# MCU.net
KiCad netlist of a schematic drawn in Altium Designer
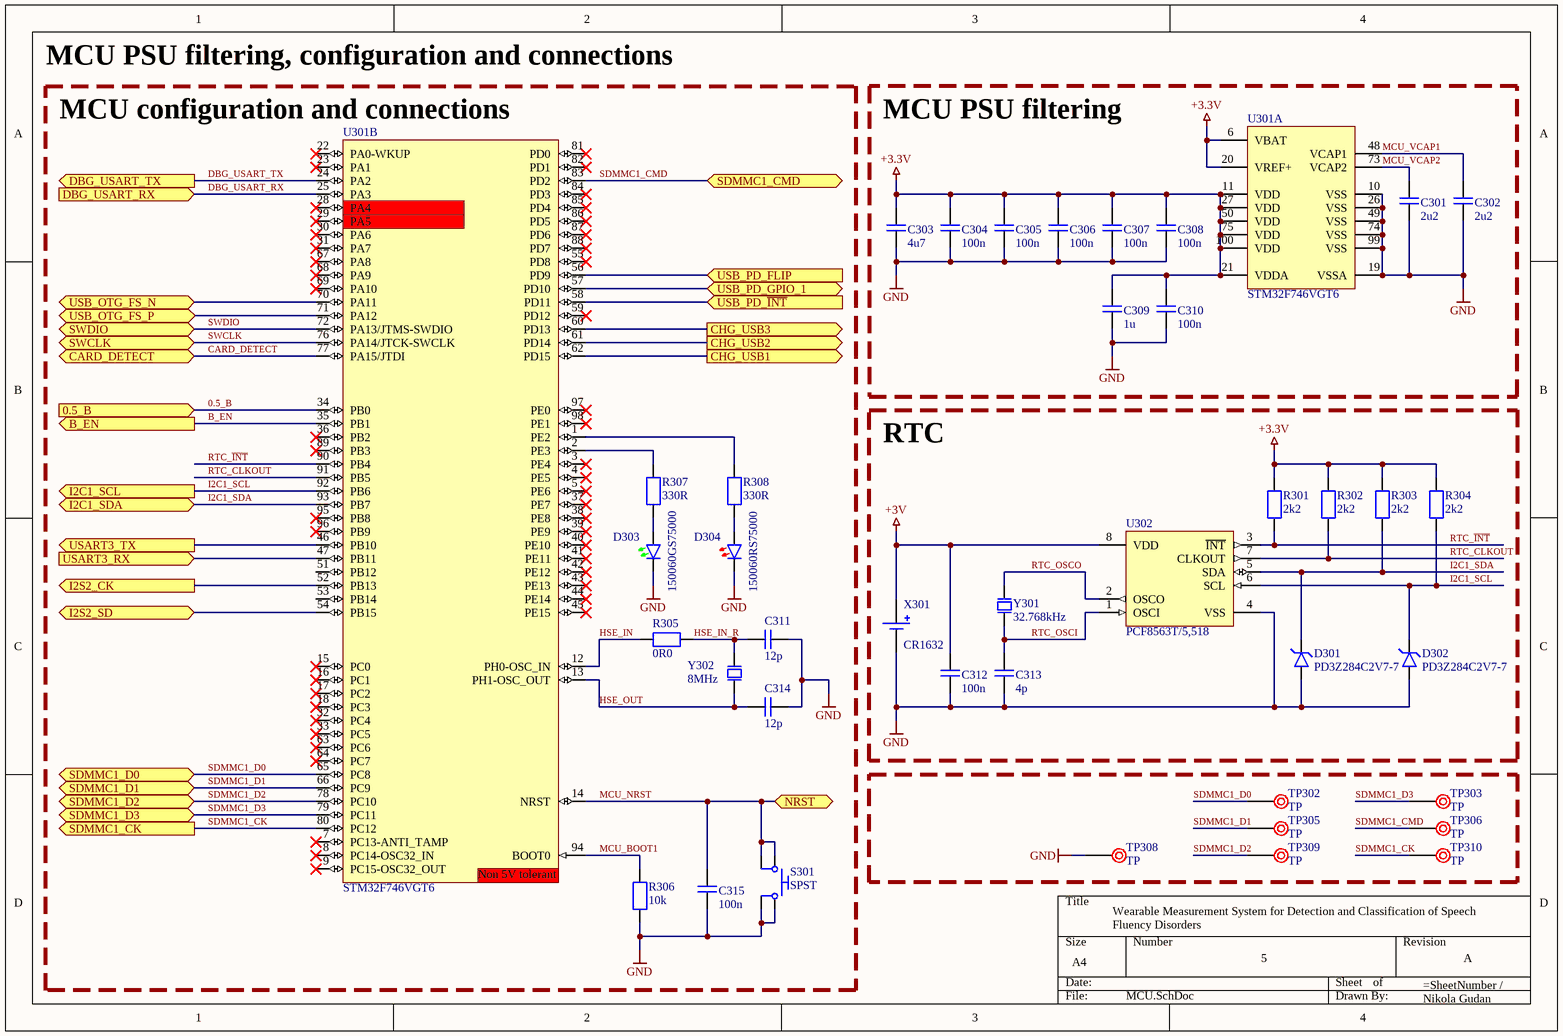
[diagram p0: MCU.SchDoc]

(export (version "E")
  (design (tool "Eeschema 10.0.6"))
  (components
    (comp (ref "C301")
      (value "2u2")
      (footprint "CAPC0603")
      (description "Ceramic capacitor, VAL?,  VOL?, DIEL?")
      (fields (field (name "MFR") "?") (field (name "CHECKED") "Yes"))
      (libsource (lib "NG_Passive") (part "CAPC0603"))
    )
    (comp (ref "C302")
      (value "2u2")
      (footprint "CAPC0603")
      (description "Ceramic capacitor, VAL?,  VOL?, DIEL?")
      (fields (field (name "MFR") "?") (field (name "CHECKED") "Yes"))
      (libsource (lib "NG_Passive") (part "CAPC0603"))
    )
    (comp (ref "C303")
      (value "4u7")
      (footprint "CAPC0603")
      (description "Ceramic capacitor, VAL?,  VOL?, DIEL?")
      (fields (field (name "MFR") "?") (field (name "CHECKED") "Yes"))
      (libsource (lib "NG_Passive") (part "CAPC0603"))
    )
    (comp (ref "C304")
      (value "100n")
      (footprint "CAPC0603")
      (description "Ceramic capacitor, VAL?,  VOL?, DIEL?")
      (fields (field (name "MFR") "?") (field (name "CHECKED") "Yes"))
      (libsource (lib "NG_Passive") (part "CAPC0603"))
    )
    (comp (ref "C305")
      (value "100n")
      (footprint "CAPC0603")
      (description "Ceramic capacitor, VAL?,  VOL?, DIEL?")
      (fields (field (name "MFR") "?") (field (name "CHECKED") "Yes"))
      (libsource (lib "NG_Passive") (part "CAPC0603"))
    )
    (comp (ref "C306")
      (value "100n")
      (footprint "CAPC0603")
      (description "Ceramic capacitor, VAL?,  VOL?, DIEL?")
      (fields (field (name "MFR") "?") (field (name "CHECKED") "Yes"))
      (libsource (lib "NG_Passive") (part "CAPC0603"))
    )
    (comp (ref "C307")
      (value "100n")
      (footprint "CAPC0603")
      (description "Ceramic capacitor, VAL?,  VOL?, DIEL?")
      (fields (field (name "MFR") "?") (field (name "CHECKED") "Yes"))
      (libsource (lib "NG_Passive") (part "CAPC0603"))
    )
    (comp (ref "C308")
      (value "100n")
      (footprint "CAPC0603")
      (description "Ceramic capacitor, VAL?,  VOL?, DIEL?")
      (fields (field (name "MFR") "?") (field (name "CHECKED") "Yes"))
      (libsource (lib "NG_Passive") (part "CAPC0603"))
    )
    (comp (ref "C309")
      (value "1u")
      (footprint "CAPC0603")
      (description "Ceramic capacitor, VAL?,  VOL?, DIEL?")
      (fields (field (name "MFR") "?") (field (name "CHECKED") "Yes"))
      (libsource (lib "NG_Passive") (part "CAPC0603"))
    )
    (comp (ref "C310")
      (value "100n")
      (footprint "CAPC0603")
      (description "Ceramic capacitor, VAL?,  VOL?, DIEL?")
      (fields (field (name "MFR") "?") (field (name "CHECKED") "Yes"))
      (libsource (lib "NG_Passive") (part "CAPC0603"))
    )
    (comp (ref "C311")
      (value "12p")
      (footprint "CAPC0603")
      (description "Ceramic capacitor, VAL?,  VOL?, DIEL?")
      (fields (field (name "MFR") "?") (field (name "CHECKED") "Yes"))
      (libsource (lib "NG_Passive") (part "CAPC0603"))
    )
    (comp (ref "C312")
      (value "100n")
      (footprint "CAPC0603")
      (description "Ceramic capacitor, VAL?,  VOL?, DIEL?")
      (fields (field (name "MFR") "?") (field (name "CHECKED") "Yes"))
      (libsource (lib "NG_Passive") (part "CAPC0603"))
    )
    (comp (ref "C313")
      (value "4p")
      (footprint "CAPC0603")
      (description "Ceramic capacitor, VAL?,  VOL?, DIEL?")
      (fields (field (name "MFR") "?") (field (name "CHECKED") "Yes"))
      (libsource (lib "NG_Passive") (part "CAPC0603"))
    )
    (comp (ref "C314")
      (value "12p")
      (footprint "CAPC0603")
      (description "Ceramic capacitor, VAL?,  VOL?, DIEL?")
      (fields (field (name "MFR") "?") (field (name "CHECKED") "Yes"))
      (libsource (lib "NG_Passive") (part "CAPC0603"))
    )
    (comp (ref "C315")
      (value "100n")
      (footprint "CAPC0603")
      (description "Ceramic capacitor, VAL?,  VOL?, DIEL?")
      (fields (field (name "MFR") "?") (field (name "CHECKED") "Yes"))
      (libsource (lib "NG_Passive") (part "CAPC0603"))
    )
    (comp (ref "D301")
      (value "PD3Z284C2V7-7")
      (footprint "PowerDI323")
      (description "Zener Dioode, 2.7V, 500mW")
      (fields
        (field (name "MFR") "Diodes Incorporated")
        (field (name "LCSC PART NUMBER") "C531171")
        (field (name "CHECKED") "Yes")
      )
      (libsource (lib "NG_Active") (part "PD3Z284C2V7-7"))
    )
    (comp (ref "D302")
      (value "PD3Z284C2V7-7")
      (footprint "PowerDI323")
      (description "Zener Dioode, 2.7V, 500mW")
      (fields
        (field (name "MFR") "Diodes Incorporated")
        (field (name "LCSC PART NUMBER") "C531171")
        (field (name "CHECKED") "Yes")
      )
      (libsource (lib "NG_Active") (part "PD3Z284C2V7-7"))
    )
    (comp (ref "D303")
      (value "150060GS75000")
      (footprint "LED0603")
      (description "LED Green, 2.1V, 20mA")
      (fields
        (field (name "MFR") "Würth Elektronik")
        (field (name "LCSC PART NUMBER") "C913102")
        (field (name "CHECKED") "Yes")
      )
      (libsource (lib "NG_Active") (part "LTST-C194KGKT"))
    )
    (comp (ref "D304")
      (value "150060RS75000")
      (footprint "LED0603")
      (description "LED Red, 2.3V, 20mA")
      (fields
        (field (name "MFR") "Würth Elektronik")
        (field (name "LCSC PART NUMBER") "C497931")
        (field (name "CHECKED") "Yes")
      )
      (libsource (lib "NG_Active") (part "HL-PST-1608S9AC-04"))
    )
    (comp (ref "R301")
      (value "2k2")
      (footprint "RESC0603")
      (description "Thick film resistor, VAL?, POW?")
      (fields (field (name "MFR") "?") (field (name "CHECKED") "Yes"))
      (libsource (lib "NG_Passive") (part "RES0603"))
    )
    (comp (ref "R302")
      (value "2k2")
      (footprint "RESC0603")
      (description "Thick film resistor, VAL?, POW?")
      (fields (field (name "MFR") "?") (field (name "CHECKED") "Yes"))
      (libsource (lib "NG_Passive") (part "RES0603"))
    )
    (comp (ref "R303")
      (value "2k2")
      (footprint "RESC0603")
      (description "Thick film resistor, VAL?, POW?")
      (fields (field (name "MFR") "?") (field (name "CHECKED") "Yes"))
      (libsource (lib "NG_Passive") (part "RES0603"))
    )
    (comp (ref "R304")
      (value "2k2")
      (footprint "RESC0603")
      (description "Thick film resistor, VAL?, POW?")
      (fields (field (name "MFR") "?") (field (name "CHECKED") "Yes"))
      (libsource (lib "NG_Passive") (part "RES0603"))
    )
    (comp (ref "R305")
      (value "0R0")
      (footprint "RESC0603")
      (description "Thick film resistor, VAL?, POW?")
      (fields (field (name "MFR") "?") (field (name "CHECKED") "Yes"))
      (libsource (lib "NG_Passive") (part "RES0603"))
    )
    (comp (ref "R306")
      (value "10k")
      (footprint "RESC0603")
      (description "Thick film resistor, VAL?, POW?")
      (fields (field (name "MFR") "?") (field (name "CHECKED") "Yes"))
      (libsource (lib "NG_Passive") (part "RES0603"))
    )
    (comp (ref "R307")
      (value "330R")
      (footprint "RESC0603")
      (description "Thick film resistor, VAL?, POW?")
      (fields (field (name "MFR") "?") (field (name "CHECKED") "Yes"))
      (libsource (lib "NG_Passive") (part "RES0603"))
    )
    (comp (ref "R308")
      (value "330R")
      (footprint "RESC0603")
      (description "Thick film resistor, VAL?, POW?")
      (fields (field (name "MFR") "?") (field (name "CHECKED") "Yes"))
      (libsource (lib "NG_Passive") (part "RES0603"))
    )
    (comp (ref "S301")
      (value "SPST")
      (footprint "SW_TSA063G60-250")
      (description "TACT SW, SPST, NO")
      (fields
        (field (name "MFR") "C&K")
        (field (name "LCSC PART NUMBER") "C294566")
        (field (name "CHECKED") "Yes")
      )
      (libsource (lib "NG_Mechanical") (part "TACT SW"))
    )
    (comp (ref "TP302")
      (value "TP")
      (footprint "TESTPOINT")
      (description "Testpoint")
      (fields
        (field (name "MFR") "Keystone")
        (field (name "LCSC PART NUMBER") "C238122")
        (field (name "CHECKED") "Yes")
      )
      (libsource (lib "NG_Mechanical") (part "TESTPOINT"))
    )
    (comp (ref "TP303")
      (value "TP")
      (footprint "TESTPOINT")
      (description "Testpoint")
      (fields
        (field (name "MFR") "Keystone")
        (field (name "LCSC PART NUMBER") "C238122")
        (field (name "CHECKED") "Yes")
      )
      (libsource (lib "NG_Mechanical") (part "TESTPOINT"))
    )
    (comp (ref "TP305")
      (value "TP")
      (footprint "TESTPOINT")
      (description "Testpoint")
      (fields
        (field (name "MFR") "Keystone")
        (field (name "LCSC PART NUMBER") "C238122")
        (field (name "CHECKED") "Yes")
      )
      (libsource (lib "NG_Mechanical") (part "TESTPOINT"))
    )
    (comp (ref "TP306")
      (value "TP")
      (footprint "TESTPOINT")
      (description "Testpoint")
      (fields
        (field (name "MFR") "Keystone")
        (field (name "LCSC PART NUMBER") "C238122")
        (field (name "CHECKED") "Yes")
      )
      (libsource (lib "NG_Mechanical") (part "TESTPOINT"))
    )
    (comp (ref "TP308")
      (value "TP")
      (footprint "TESTPOINT")
      (description "Testpoint")
      (fields
        (field (name "MFR") "Keystone")
        (field (name "LCSC PART NUMBER") "C238122")
        (field (name "CHECKED") "Yes")
      )
      (libsource (lib "NG_Mechanical") (part "TESTPOINT"))
    )
    (comp (ref "TP309")
      (value "TP")
      (footprint "TESTPOINT")
      (description "Testpoint")
      (fields
        (field (name "MFR") "Keystone")
        (field (name "LCSC PART NUMBER") "C238122")
        (field (name "CHECKED") "Yes")
      )
      (libsource (lib "NG_Mechanical") (part "TESTPOINT"))
    )
    (comp (ref "TP310")
      (value "TP")
      (footprint "TESTPOINT")
      (description "Testpoint")
      (fields
        (field (name "MFR") "Keystone")
        (field (name "LCSC PART NUMBER") "C238122")
        (field (name "CHECKED") "Yes")
      )
      (libsource (lib "NG_Mechanical") (part "TESTPOINT"))
    )
    (comp (ref "U301")
      (value "STM32F746VGT6")
      (footprint "QFP50P1600X1600X160-100")
      (fields
        (field (name "MFR") "STMicroelectronics")
        (field (name "LCSC PART NUMBER") "C87664")
        (field (name "CHECKED") "Yes")
      )
      (libsource (lib "NG_Digital") (part "STM32F746VGT6"))
    )
    (comp (ref "U302")
      (value "PCF8563T/5,518")
      (footprint "SOIC127P610X175-8")
      (description "IC RTC CLOCK/CALENDAR I2C 8SO")
      (fields
        (field (name "MFR") "NXP USA Inc.")
        (field (name "LCSC PART NUMBER") "C7440")
        (field (name "CHECKED") "Yes")
      )
      (libsource (lib "NG_Digital") (part "PCF8563T/5,518"))
    )
    (comp (ref "X301")
      (value "CR1632")
      (footprint "BAT_504TR")
      (description "CR1632 Battery Holder")
      (fields
        (field (name "MFR") "Keystone Electronics")
        (field (name "LCSC PART NUMBER") "C964735")
        (field (name "CHECKED") "Yes")
      )
      (libsource (lib "NG_Mechanical") (part "CR1632"))
    )
    (comp (ref "Y301")
      (value "32.768kHz")
      (footprint "XTAL320X150X80")
      (description "Crystal, 32.768Hz, 9pF, 50kOhms")
      (fields
        (field (name "MFR") "Seiko Epson")
        (field (name "LCSC PART NUMBER") "C1987155")
        (field (name "CHECKED") "Yes")
      )
      (libsource (lib "NG_Passive") (part "X1A0001410002"))
    )
    (comp (ref "Y302")
      (value "8MHz")
      (footprint "XTAL800X450X180")
      (description "Crystal, 8MHz, 8pF, 200Ohms")
      (fields
        (field (name "MFR") "NDK")
        (field (name "LCSC PART NUMBER") "C1985641")
        (field (name "CHECKED") "Yes")
      )
      (libsource (lib "NG_Passive") (part "NX8045GB-8.000000MHZ"))
    )
  )
  (nets
    (net (code "1") (name "+3.3V") (class "Default")
      (node (ref "C303") (pin "2") (pinfunction "2_2") (pintype "passive"))
      (node (ref "C304") (pin "2") (pinfunction "2_2") (pintype "passive"))
      (node (ref "C305") (pin "2") (pinfunction "2_2") (pintype "passive"))
      (node (ref "C306") (pin "2") (pinfunction "2_2") (pintype "passive"))
      (node (ref "C307") (pin "2") (pinfunction "2_2") (pintype "passive"))
      (node (ref "C308") (pin "2") (pinfunction "2_2") (pintype "passive"))
      (node (ref "C309") (pin "2") (pinfunction "2_2") (pintype "passive"))
      (node (ref "C310") (pin "2") (pinfunction "2_2") (pintype "passive"))
      (node (ref "R301") (pin "2") (pinfunction "2_2") (pintype "passive"))
      (node (ref "R302") (pin "2") (pinfunction "2_2") (pintype "passive"))
      (node (ref "R303") (pin "2") (pinfunction "2_2") (pintype "passive"))
      (node (ref "R304") (pin "2") (pinfunction "2_2") (pintype "passive"))
      (node (ref "U301") (pin "100") (pinfunction "VDD_100") (pintype "power_in"))
      (node (ref "U301") (pin "11") (pinfunction "VDD_11") (pintype "power_in"))
      (node (ref "U301") (pin "20") (pinfunction "VREF+_20") (pintype "power_in"))
      (node (ref "U301") (pin "21") (pinfunction "VDDA_21") (pintype "power_in"))
      (node (ref "U301") (pin "27") (pinfunction "VDD_27") (pintype "power_in"))
      (node (ref "U301") (pin "50") (pinfunction "VDD_50") (pintype "power_in"))
      (node (ref "U301") (pin "6") (pinfunction "VBAT_6") (pintype "power_in"))
      (node (ref "U301") (pin "75") (pinfunction "VDD_75") (pintype "power_in"))
    )
    (net (code "2") (name "+3V") (class "Default")
      (node (ref "C312") (pin "2") (pinfunction "2_2") (pintype "passive"))
      (node (ref "U302") (pin "8") (pinfunction "VDD_8") (pintype "power_in"))
      (node (ref "X301") (pin "1") (pinfunction "P_1") (pintype "power_in"))
    )
    (net (code "3") (name "/0.5_B") (class "Default")
      (node (ref "U301") (pin "34") (pinfunction "PB0_34") (pintype "bidirectional"))
    )
    (net (code "4") (name "/B_EN") (class "Default")
      (node (ref "U301") (pin "35") (pinfunction "PB1_35") (pintype "bidirectional"))
    )
    (net (code "5") (name "/CARD_DETECT") (class "Default")
      (node (ref "U301") (pin "77") (pinfunction "PA15/JTDI_77") (pintype "bidirectional"))
    )
    (net (code "6") (name "/CHG_USB1") (class "Default")
      (node (ref "U301") (pin "62") (pinfunction "PD15_62") (pintype "bidirectional"))
    )
    (net (code "7") (name "/CHG_USB2") (class "Default")
      (node (ref "U301") (pin "61") (pinfunction "PD14_61") (pintype "bidirectional"))
    )
    (net (code "8") (name "/CHG_USB3") (class "Default")
      (node (ref "U301") (pin "60") (pinfunction "PD13_60") (pintype "bidirectional"))
    )
    (net (code "9") (name "/DBG_USART_RX") (class "Default")
      (node (ref "U301") (pin "25") (pinfunction "PA3_25") (pintype "bidirectional"))
    )
    (net (code "10") (name "/DBG_USART_TX") (class "Default")
      (node (ref "U301") (pin "24") (pinfunction "PA2_24") (pintype "bidirectional"))
    )
    (net (code "11") (name "/HSE_IN") (class "Default")
      (node (ref "R305") (pin "2") (pinfunction "2_2") (pintype "passive"))
      (node (ref "U301") (pin "12") (pinfunction "PH0-OSC_IN_12") (pintype "bidirectional"))
    )
    (net (code "12") (name "/HSE_IN_R") (class "Default")
      (node (ref "C311") (pin "1") (pinfunction "1_1") (pintype "passive"))
      (node (ref "R305") (pin "1") (pinfunction "1_1") (pintype "passive"))
      (node (ref "Y302") (pin "2") (pinfunction "2_2") (pintype "passive"))
    )
    (net (code "13") (name "/HSE_OUT") (class "Default")
      (node (ref "C314") (pin "1") (pinfunction "1_1") (pintype "passive"))
      (node (ref "U301") (pin "13") (pinfunction "PH1-OSC_OUT_13") (pintype "bidirectional"))
      (node (ref "Y302") (pin "1") (pinfunction "1_1") (pintype "passive"))
    )
    (net (code "14") (name "/I2C1_SCL") (class "Default")
      (node (ref "D302") (pin "1") (pinfunction "1_1") (pintype "passive"))
      (node (ref "R304") (pin "1") (pinfunction "1_1") (pintype "passive"))
      (node (ref "U301") (pin "92") (pinfunction "PB6_92") (pintype "bidirectional"))
      (node (ref "U302") (pin "6") (pinfunction "SCL_6") (pintype "input"))
    )
    (net (code "15") (name "/I2C1_SDA") (class "Default")
      (node (ref "D301") (pin "1") (pinfunction "1_1") (pintype "passive"))
      (node (ref "R303") (pin "1") (pinfunction "1_1") (pintype "passive"))
      (node (ref "U301") (pin "93") (pinfunction "PB7_93") (pintype "bidirectional"))
      (node (ref "U302") (pin "5") (pinfunction "SDA_5") (pintype "bidirectional"))
    )
    (net (code "16") (name "/I2S2_CK") (class "Default")
      (node (ref "U301") (pin "52") (pinfunction "PB13_52") (pintype "bidirectional"))
    )
    (net (code "17") (name "/I2S2_SD") (class "Default")
      (node (ref "U301") (pin "54") (pinfunction "PB15_54") (pintype "bidirectional"))
    )
    (net (code "18") (name "/MCU_BOOT1") (class "Default")
      (node (ref "R306") (pin "2") (pinfunction "2_2") (pintype "passive"))
      (node (ref "U301") (pin "94") (pinfunction "BOOT0_94") (pintype "input"))
    )
    (net (code "19") (name "/MCU_NRST") (class "Default")
      (node (ref "C315") (pin "2") (pinfunction "2_2") (pintype "passive"))
      (node (ref "S301") (pin "1") (pinfunction "1_1") (pintype "passive"))
      (node (ref "S301") (pin "2") (pinfunction "2_2") (pintype "passive"))
      (node (ref "U301") (pin "14") (pinfunction "NRST_14") (pintype "bidirectional"))
    )
    (net (code "20") (name "/MCU_VCAP1") (class "Default")
      (node (ref "C302") (pin "2") (pinfunction "2_2") (pintype "passive"))
      (node (ref "U301") (pin "48") (pinfunction "VCAP1_48") (pintype "power_in"))
    )
    (net (code "21") (name "/MCU_VCAP2") (class "Default")
      (node (ref "C301") (pin "2") (pinfunction "2_2") (pintype "passive"))
      (node (ref "U301") (pin "73") (pinfunction "VCAP2_73") (pintype "power_in"))
    )
    (net (code "22") (name "/RTC_CLKOUT") (class "Default")
      (node (ref "R302") (pin "1") (pinfunction "1_1") (pintype "passive"))
      (node (ref "U301") (pin "91") (pinfunction "PB5_91") (pintype "bidirectional"))
      (node (ref "U302") (pin "7") (pinfunction "CLKOUT_7") (pintype "output"))
    )
    (net (code "23") (name "/RTC_OSCI") (class "Default")
      (node (ref "C313") (pin "2") (pinfunction "2_2") (pintype "passive"))
      (node (ref "U302") (pin "1") (pinfunction "OSCI_1") (pintype "input"))
      (node (ref "Y301") (pin "1") (pinfunction "1_1") (pintype "passive"))
    )
    (net (code "24") (name "/RTC_OSCO") (class "Default")
      (node (ref "U302") (pin "2") (pinfunction "OSCO_2") (pintype "output"))
      (node (ref "Y301") (pin "2") (pinfunction "2_2") (pintype "passive"))
    )
    (net (code "25") (name "/RTC_~{INT}") (class "Default")
      (node (ref "R301") (pin "1") (pinfunction "1_1") (pintype "passive"))
      (node (ref "U301") (pin "90") (pinfunction "PB4_90") (pintype "bidirectional"))
      (node (ref "U302") (pin "3") (pinfunction "~{INT}_3") (pintype "output"))
    )
    (net (code "26") (name "/SDMMC1_CK") (class "Default")
      (node (ref "TP310") (pin "1") (pinfunction "1_1") (pintype "passive"))
      (node (ref "U301") (pin "80") (pinfunction "PC12_80") (pintype "bidirectional"))
    )
    (net (code "27") (name "/SDMMC1_CMD") (class "Default")
      (node (ref "TP306") (pin "1") (pinfunction "1_1") (pintype "passive"))
      (node (ref "U301") (pin "83") (pinfunction "PD2_83") (pintype "bidirectional"))
    )
    (net (code "28") (name "/SDMMC1_D0") (class "Default")
      (node (ref "TP302") (pin "1") (pinfunction "1_1") (pintype "passive"))
      (node (ref "U301") (pin "65") (pinfunction "PC8_65") (pintype "bidirectional"))
    )
    (net (code "29") (name "/SDMMC1_D1") (class "Default")
      (node (ref "TP305") (pin "1") (pinfunction "1_1") (pintype "passive"))
      (node (ref "U301") (pin "66") (pinfunction "PC9_66") (pintype "bidirectional"))
    )
    (net (code "30") (name "/SDMMC1_D2") (class "Default")
      (node (ref "TP309") (pin "1") (pinfunction "1_1") (pintype "passive"))
      (node (ref "U301") (pin "78") (pinfunction "PC10_78") (pintype "bidirectional"))
    )
    (net (code "31") (name "/SDMMC1_D3") (class "Default")
      (node (ref "TP303") (pin "1") (pinfunction "1_1") (pintype "passive"))
      (node (ref "U301") (pin "79") (pinfunction "PC11_79") (pintype "bidirectional"))
    )
    (net (code "32") (name "/SWCLK") (class "Default")
      (node (ref "U301") (pin "76") (pinfunction "PA14/JTCK-SWCLK_76") (pintype "bidirectional"))
    )
    (net (code "33") (name "/SWDIO") (class "Default")
      (node (ref "U301") (pin "72") (pinfunction "PA13/JTMS-SWDIO_72") (pintype "bidirectional"))
    )
    (net (code "34") (name "/USART3_RX") (class "Default")
      (node (ref "U301") (pin "47") (pinfunction "PB11_47") (pintype "bidirectional"))
    )
    (net (code "35") (name "/USART3_TX") (class "Default")
      (node (ref "U301") (pin "46") (pinfunction "PB10_46") (pintype "bidirectional"))
    )
    (net (code "36") (name "/USB_OTG_FS_N") (class "Default")
      (node (ref "U301") (pin "70") (pinfunction "PA11_70") (pintype "bidirectional"))
    )
    (net (code "37") (name "/USB_OTG_FS_P") (class "Default")
      (node (ref "U301") (pin "71") (pinfunction "PA12_71") (pintype "bidirectional"))
    )
    (net (code "38") (name "/USB_PD_FLIP") (class "Default")
      (node (ref "U301") (pin "56") (pinfunction "PD9_56") (pintype "bidirectional"))
    )
    (net (code "39") (name "/USB_PD_GPIO_1") (class "Default")
      (node (ref "U301") (pin "57") (pinfunction "PD10_57") (pintype "bidirectional"))
    )
    (net (code "40") (name "/USB_PD_~{INT}") (class "Default")
      (node (ref "U301") (pin "58") (pinfunction "PD11_58") (pintype "bidirectional"))
    )
    (net (code "41") (name "GND") (class "Default")
      (node (ref "C301") (pin "1") (pinfunction "1_1") (pintype "passive"))
      (node (ref "C302") (pin "1") (pinfunction "1_1") (pintype "passive"))
      (node (ref "C303") (pin "1") (pinfunction "1_1") (pintype "passive"))
      (node (ref "C304") (pin "1") (pinfunction "1_1") (pintype "passive"))
      (node (ref "C305") (pin "1") (pinfunction "1_1") (pintype "passive"))
      (node (ref "C306") (pin "1") (pinfunction "1_1") (pintype "passive"))
      (node (ref "C307") (pin "1") (pinfunction "1_1") (pintype "passive"))
      (node (ref "C308") (pin "1") (pinfunction "1_1") (pintype "passive"))
      (node (ref "C309") (pin "1") (pinfunction "1_1") (pintype "passive"))
      (node (ref "C310") (pin "1") (pinfunction "1_1") (pintype "passive"))
      (node (ref "C311") (pin "2") (pinfunction "2_2") (pintype "passive"))
      (node (ref "C312") (pin "1") (pinfunction "1_1") (pintype "passive"))
      (node (ref "C313") (pin "1") (pinfunction "1_1") (pintype "passive"))
      (node (ref "C314") (pin "2") (pinfunction "2_2") (pintype "passive"))
      (node (ref "C315") (pin "1") (pinfunction "1_1") (pintype "passive"))
      (node (ref "D301") (pin "2") (pinfunction "2_2") (pintype "passive"))
      (node (ref "D302") (pin "2") (pinfunction "2_2") (pintype "passive"))
      (node (ref "D303") (pin "1") (pinfunction "1_1") (pintype "passive"))
      (node (ref "D304") (pin "1") (pinfunction "1_1") (pintype "passive"))
      (node (ref "R306") (pin "1") (pinfunction "1_1") (pintype "passive"))
      (node (ref "S301") (pin "3") (pinfunction "3_3") (pintype "power_in"))
      (node (ref "S301") (pin "4") (pinfunction "4_4") (pintype "power_in"))
      (node (ref "TP308") (pin "1") (pinfunction "1_1") (pintype "passive"))
      (node (ref "U301") (pin "10") (pinfunction "VSS_10") (pintype "power_in"))
      (node (ref "U301") (pin "19") (pinfunction "VSSA_19") (pintype "power_in"))
      (node (ref "U301") (pin "26") (pinfunction "VSS_26") (pintype "power_in"))
      (node (ref "U301") (pin "49") (pinfunction "VSS_49") (pintype "power_in"))
      (node (ref "U301") (pin "74") (pinfunction "VSS_74") (pintype "power_in"))
      (node (ref "U301") (pin "99") (pinfunction "VSS_99") (pintype "power_in"))
      (node (ref "U302") (pin "4") (pinfunction "VSS_4") (pintype "power_in"))
      (node (ref "X301") (pin "2") (pinfunction "N_2") (pintype "power_in"))
    )
    (net (code "42") (name "Net-(D303-Pad2)") (class "Default")
      (node (ref "D303") (pin "2") (pinfunction "2_2") (pintype "passive"))
      (node (ref "R307") (pin "1") (pinfunction "1_1") (pintype "passive"))
    )
    (net (code "43") (name "Net-(D304-Pad2)") (class "Default")
      (node (ref "D304") (pin "2") (pinfunction "2_2") (pintype "passive"))
      (node (ref "R308") (pin "1") (pinfunction "1_1") (pintype "passive"))
    )
    (net (code "44") (name "Net-(U301B-PE2)") (class "Default")
      (node (ref "R308") (pin "2") (pinfunction "2_2") (pintype "passive"))
      (node (ref "U301") (pin "1") (pinfunction "PE2_1") (pintype "bidirectional"))
    )
    (net (code "45") (name "Net-(U301B-PE3)") (class "Default")
      (node (ref "R307") (pin "2") (pinfunction "2_2") (pintype "passive"))
      (node (ref "U301") (pin "2") (pinfunction "PE3_2") (pintype "bidirectional"))
    )
    (net (code "46") (name "unconnected-(U301B-PA0-WKUP-Pad22)") (class "Default")
      (node (ref "U301") (pin "22") (pinfunction "PA0-WKUP_22") (pintype "bidirectional+no_connect"))
    )
    (net (code "47") (name "unconnected-(U301B-PA1-Pad23)") (class "Default")
      (node (ref "U301") (pin "23") (pinfunction "PA1_23") (pintype "bidirectional+no_connect"))
    )
    (net (code "48") (name "unconnected-(U301B-PA4-Pad28)") (class "Default")
      (node (ref "U301") (pin "28") (pinfunction "PA4_28") (pintype "bidirectional+no_connect"))
    )
    (net (code "49") (name "unconnected-(U301B-PA5-Pad29)") (class "Default")
      (node (ref "U301") (pin "29") (pinfunction "PA5_29") (pintype "bidirectional+no_connect"))
    )
    (net (code "50") (name "unconnected-(U301B-PA6-Pad30)") (class "Default")
      (node (ref "U301") (pin "30") (pinfunction "PA6_30") (pintype "bidirectional+no_connect"))
    )
    (net (code "51") (name "unconnected-(U301B-PA7-Pad31)") (class "Default")
      (node (ref "U301") (pin "31") (pinfunction "PA7_31") (pintype "bidirectional+no_connect"))
    )
    (net (code "52") (name "unconnected-(U301B-PA8-Pad67)") (class "Default")
      (node (ref "U301") (pin "67") (pinfunction "PA8_67") (pintype "bidirectional+no_connect"))
    )
    (net (code "53") (name "unconnected-(U301B-PA9-Pad68)") (class "Default")
      (node (ref "U301") (pin "68") (pinfunction "PA9_68") (pintype "bidirectional+no_connect"))
    )
    (net (code "54") (name "unconnected-(U301B-PA10-Pad69)") (class "Default")
      (node (ref "U301") (pin "69") (pinfunction "PA10_69") (pintype "bidirectional+no_connect"))
    )
    (net (code "55") (name "unconnected-(U301B-PB2-Pad36)") (class "Default")
      (node (ref "U301") (pin "36") (pinfunction "PB2_36") (pintype "bidirectional+no_connect"))
    )
    (net (code "56") (name "unconnected-(U301B-PB3-Pad89)") (class "Default")
      (node (ref "U301") (pin "89") (pinfunction "PB3_89") (pintype "bidirectional+no_connect"))
    )
    (net (code "57") (name "unconnected-(U301B-PB8-Pad95)") (class "Default")
      (node (ref "U301") (pin "95") (pinfunction "PB8_95") (pintype "bidirectional+no_connect"))
    )
    (net (code "58") (name "unconnected-(U301B-PB9-Pad96)") (class "Default")
      (node (ref "U301") (pin "96") (pinfunction "PB9_96") (pintype "bidirectional+no_connect"))
    )
    (net (code "59") (name "unconnected-(U301B-PB12-Pad51)") (class "Default")
      (node (ref "U301") (pin "51") (pinfunction "PB12_51") (pintype "bidirectional"))
    )
    (net (code "60") (name "unconnected-(U301B-PB14-Pad53)") (class "Default")
      (node (ref "U301") (pin "53") (pinfunction "PB14_53") (pintype "bidirectional"))
    )
    (net (code "61") (name "unconnected-(U301B-PC0-Pad15)") (class "Default")
      (node (ref "U301") (pin "15") (pinfunction "PC0_15") (pintype "bidirectional+no_connect"))
    )
    (net (code "62") (name "unconnected-(U301B-PC1-Pad16)") (class "Default")
      (node (ref "U301") (pin "16") (pinfunction "PC1_16") (pintype "bidirectional+no_connect"))
    )
    (net (code "63") (name "unconnected-(U301B-PC2-Pad17)") (class "Default")
      (node (ref "U301") (pin "17") (pinfunction "PC2_17") (pintype "bidirectional+no_connect"))
    )
    (net (code "64") (name "unconnected-(U301B-PC3-Pad18)") (class "Default")
      (node (ref "U301") (pin "18") (pinfunction "PC3_18") (pintype "bidirectional+no_connect"))
    )
    (net (code "65") (name "unconnected-(U301B-PC4-Pad32)") (class "Default")
      (node (ref "U301") (pin "32") (pinfunction "PC4_32") (pintype "bidirectional+no_connect"))
    )
    (net (code "66") (name "unconnected-(U301B-PC5-Pad33)") (class "Default")
      (node (ref "U301") (pin "33") (pinfunction "PC5_33") (pintype "bidirectional+no_connect"))
    )
    (net (code "67") (name "unconnected-(U301B-PC6-Pad63)") (class "Default")
      (node (ref "U301") (pin "63") (pinfunction "PC6_63") (pintype "bidirectional+no_connect"))
    )
    (net (code "68") (name "unconnected-(U301B-PC7-Pad64)") (class "Default")
      (node (ref "U301") (pin "64") (pinfunction "PC7_64") (pintype "bidirectional+no_connect"))
    )
    (net (code "69") (name "unconnected-(U301B-PC13-ANTI_TAMP-Pad7)") (class "Default")
      (node (ref "U301") (pin "7") (pinfunction "PC13-ANTI_TAMP_7") (pintype "bidirectional+no_connect"))
    )
    (net (code "70") (name "unconnected-(U301B-PC14-OSC32_IN-Pad8)") (class "Default")
      (node (ref "U301") (pin "8") (pinfunction "PC14-OSC32_IN_8") (pintype "bidirectional+no_connect"))
    )
    (net (code "71") (name "unconnected-(U301B-PC15-OSC32_OUT-Pad9)") (class "Default")
      (node (ref "U301") (pin "9") (pinfunction "PC15-OSC32_OUT_9") (pintype "bidirectional+no_connect"))
    )
    (net (code "72") (name "unconnected-(U301B-PD0-Pad81)") (class "Default")
      (node (ref "U301") (pin "81") (pinfunction "PD0_81") (pintype "bidirectional+no_connect"))
    )
    (net (code "73") (name "unconnected-(U301B-PD1-Pad82)") (class "Default")
      (node (ref "U301") (pin "82") (pinfunction "PD1_82") (pintype "bidirectional+no_connect"))
    )
    (net (code "74") (name "unconnected-(U301B-PD3-Pad84)") (class "Default")
      (node (ref "U301") (pin "84") (pinfunction "PD3_84") (pintype "bidirectional+no_connect"))
    )
    (net (code "75") (name "unconnected-(U301B-PD4-Pad85)") (class "Default")
      (node (ref "U301") (pin "85") (pinfunction "PD4_85") (pintype "bidirectional+no_connect"))
    )
    (net (code "76") (name "unconnected-(U301B-PD5-Pad86)") (class "Default")
      (node (ref "U301") (pin "86") (pinfunction "PD5_86") (pintype "bidirectional+no_connect"))
    )
    (net (code "77") (name "unconnected-(U301B-PD6-Pad87)") (class "Default")
      (node (ref "U301") (pin "87") (pinfunction "PD6_87") (pintype "bidirectional+no_connect"))
    )
    (net (code "78") (name "unconnected-(U301B-PD7-Pad88)") (class "Default")
      (node (ref "U301") (pin "88") (pinfunction "PD7_88") (pintype "bidirectional+no_connect"))
    )
    (net (code "79") (name "unconnected-(U301B-PD8-Pad55)") (class "Default")
      (node (ref "U301") (pin "55") (pinfunction "PD8_55") (pintype "bidirectional+no_connect"))
    )
    (net (code "80") (name "unconnected-(U301B-PD12-Pad59)") (class "Default")
      (node (ref "U301") (pin "59") (pinfunction "PD12_59") (pintype "bidirectional+no_connect"))
    )
    (net (code "81") (name "unconnected-(U301B-PE0-Pad97)") (class "Default")
      (node (ref "U301") (pin "97") (pinfunction "PE0_97") (pintype "bidirectional+no_connect"))
    )
    (net (code "82") (name "unconnected-(U301B-PE1-Pad98)") (class "Default")
      (node (ref "U301") (pin "98") (pinfunction "PE1_98") (pintype "bidirectional+no_connect"))
    )
    (net (code "83") (name "unconnected-(U301B-PE4-Pad3)") (class "Default")
      (node (ref "U301") (pin "3") (pinfunction "PE4_3") (pintype "bidirectional+no_connect"))
    )
    (net (code "84") (name "unconnected-(U301B-PE5-Pad4)") (class "Default")
      (node (ref "U301") (pin "4") (pinfunction "PE5_4") (pintype "bidirectional+no_connect"))
    )
    (net (code "85") (name "unconnected-(U301B-PE6-Pad5)") (class "Default")
      (node (ref "U301") (pin "5") (pinfunction "PE6_5") (pintype "bidirectional+no_connect"))
    )
    (net (code "86") (name "unconnected-(U301B-PE7-Pad37)") (class "Default")
      (node (ref "U301") (pin "37") (pinfunction "PE7_37") (pintype "bidirectional+no_connect"))
    )
    (net (code "87") (name "unconnected-(U301B-PE8-Pad38)") (class "Default")
      (node (ref "U301") (pin "38") (pinfunction "PE8_38") (pintype "bidirectional+no_connect"))
    )
    (net (code "88") (name "unconnected-(U301B-PE9-Pad39)") (class "Default")
      (node (ref "U301") (pin "39") (pinfunction "PE9_39") (pintype "bidirectional+no_connect"))
    )
    (net (code "89") (name "unconnected-(U301B-PE10-Pad40)") (class "Default")
      (node (ref "U301") (pin "40") (pinfunction "PE10_40") (pintype "bidirectional+no_connect"))
    )
    (net (code "90") (name "unconnected-(U301B-PE11-Pad41)") (class "Default")
      (node (ref "U301") (pin "41") (pinfunction "PE11_41") (pintype "bidirectional+no_connect"))
    )
    (net (code "91") (name "unconnected-(U301B-PE12-Pad42)") (class "Default")
      (node (ref "U301") (pin "42") (pinfunction "PE12_42") (pintype "bidirectional+no_connect"))
    )
    (net (code "92") (name "unconnected-(U301B-PE13-Pad43)") (class "Default")
      (node (ref "U301") (pin "43") (pinfunction "PE13_43") (pintype "bidirectional+no_connect"))
    )
    (net (code "93") (name "unconnected-(U301B-PE14-Pad44)") (class "Default")
      (node (ref "U301") (pin "44") (pinfunction "PE14_44") (pintype "bidirectional+no_connect"))
    )
    (net (code "94") (name "unconnected-(U301B-PE15-Pad45)") (class "Default")
      (node (ref "U301") (pin "45") (pinfunction "PE15_45") (pintype "bidirectional+no_connect"))
    )
  )
)
